# FLASH_memory.net
KiCad netlist of a schematic drawn in EAGLE
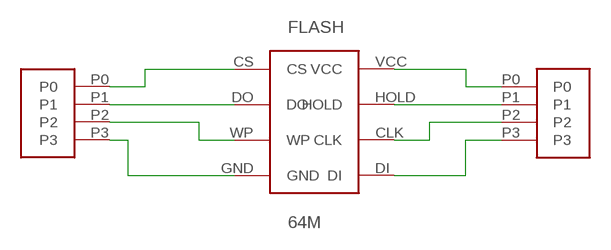
[diagram p0: schematic, sheet 1]

(export (version "E")
  (design (tool "Eeschema 10.0.6"))
  (components
    (comp (ref "FLASH")
      (value "64M")
      (footprint "eagle-import:FLASH_W25Q64FVSSIG")
      (libsource (lib "eagle-import") (part "FLASH_W25Q64FVSSIG"))
    )
    (comp (ref "U$2")
      (value "4PIN")
      (footprint "eagle-import:4PIN")
      (libsource (lib "eagle-import") (part "4PIN"))
    )
    (comp (ref "U$3")
      (value "4PIN")
      (footprint "eagle-import:4PIN")
      (libsource (lib "eagle-import") (part "4PIN"))
    )
  )
  (nets
    (net (code "1") (name "Net-(FLASH-PadCLK)") (class "Default")
      (node (ref "FLASH") (pin "CLK") (pinfunction "CLK_CLK") (pintype "bidirectional"))
      (node (ref "U$3") (pin "P2") (pinfunction "P2_P2") (pintype "bidirectional"))
    )
    (net (code "2") (name "Net-(FLASH-PadCS)") (class "Default")
      (node (ref "FLASH") (pin "CS") (pinfunction "CS_CS") (pintype "bidirectional"))
      (node (ref "U$2") (pin "P0") (pinfunction "P0_P0") (pintype "bidirectional"))
    )
    (net (code "3") (name "Net-(FLASH-PadDI)") (class "Default")
      (node (ref "FLASH") (pin "DI") (pinfunction "DI_DI") (pintype "bidirectional"))
      (node (ref "U$3") (pin "P3") (pinfunction "P3_P3") (pintype "bidirectional"))
    )
    (net (code "4") (name "Net-(FLASH-PadDO)") (class "Default")
      (node (ref "FLASH") (pin "DO") (pinfunction "DO_DO") (pintype "bidirectional"))
      (node (ref "U$2") (pin "P1") (pinfunction "P1_P1") (pintype "bidirectional"))
    )
    (net (code "5") (name "Net-(FLASH-PadGND)") (class "Default")
      (node (ref "FLASH") (pin "GND") (pinfunction "GND_GND") (pintype "bidirectional"))
      (node (ref "U$2") (pin "P3") (pinfunction "P3_P3") (pintype "bidirectional"))
    )
    (net (code "6") (name "Net-(FLASH-PadHOLD)") (class "Default")
      (node (ref "FLASH") (pin "HOLD") (pinfunction "HOLD_HOLD") (pintype "bidirectional"))
      (node (ref "U$3") (pin "P1") (pinfunction "P1_P1") (pintype "bidirectional"))
    )
    (net (code "7") (name "Net-(FLASH-PadVCC)") (class "Default")
      (node (ref "FLASH") (pin "VCC") (pinfunction "VCC_VCC") (pintype "bidirectional"))
      (node (ref "U$3") (pin "P0") (pinfunction "P0_P0") (pintype "bidirectional"))
    )
    (net (code "8") (name "Net-(FLASH-PadWP)") (class "Default")
      (node (ref "FLASH") (pin "WP") (pinfunction "WP_WP") (pintype "bidirectional"))
      (node (ref "U$2") (pin "P2") (pinfunction "P2_P2") (pintype "bidirectional"))
    )
  )
)
